# App_Board_V1_31.net
KiCad netlist of a schematic drawn in EAGLE
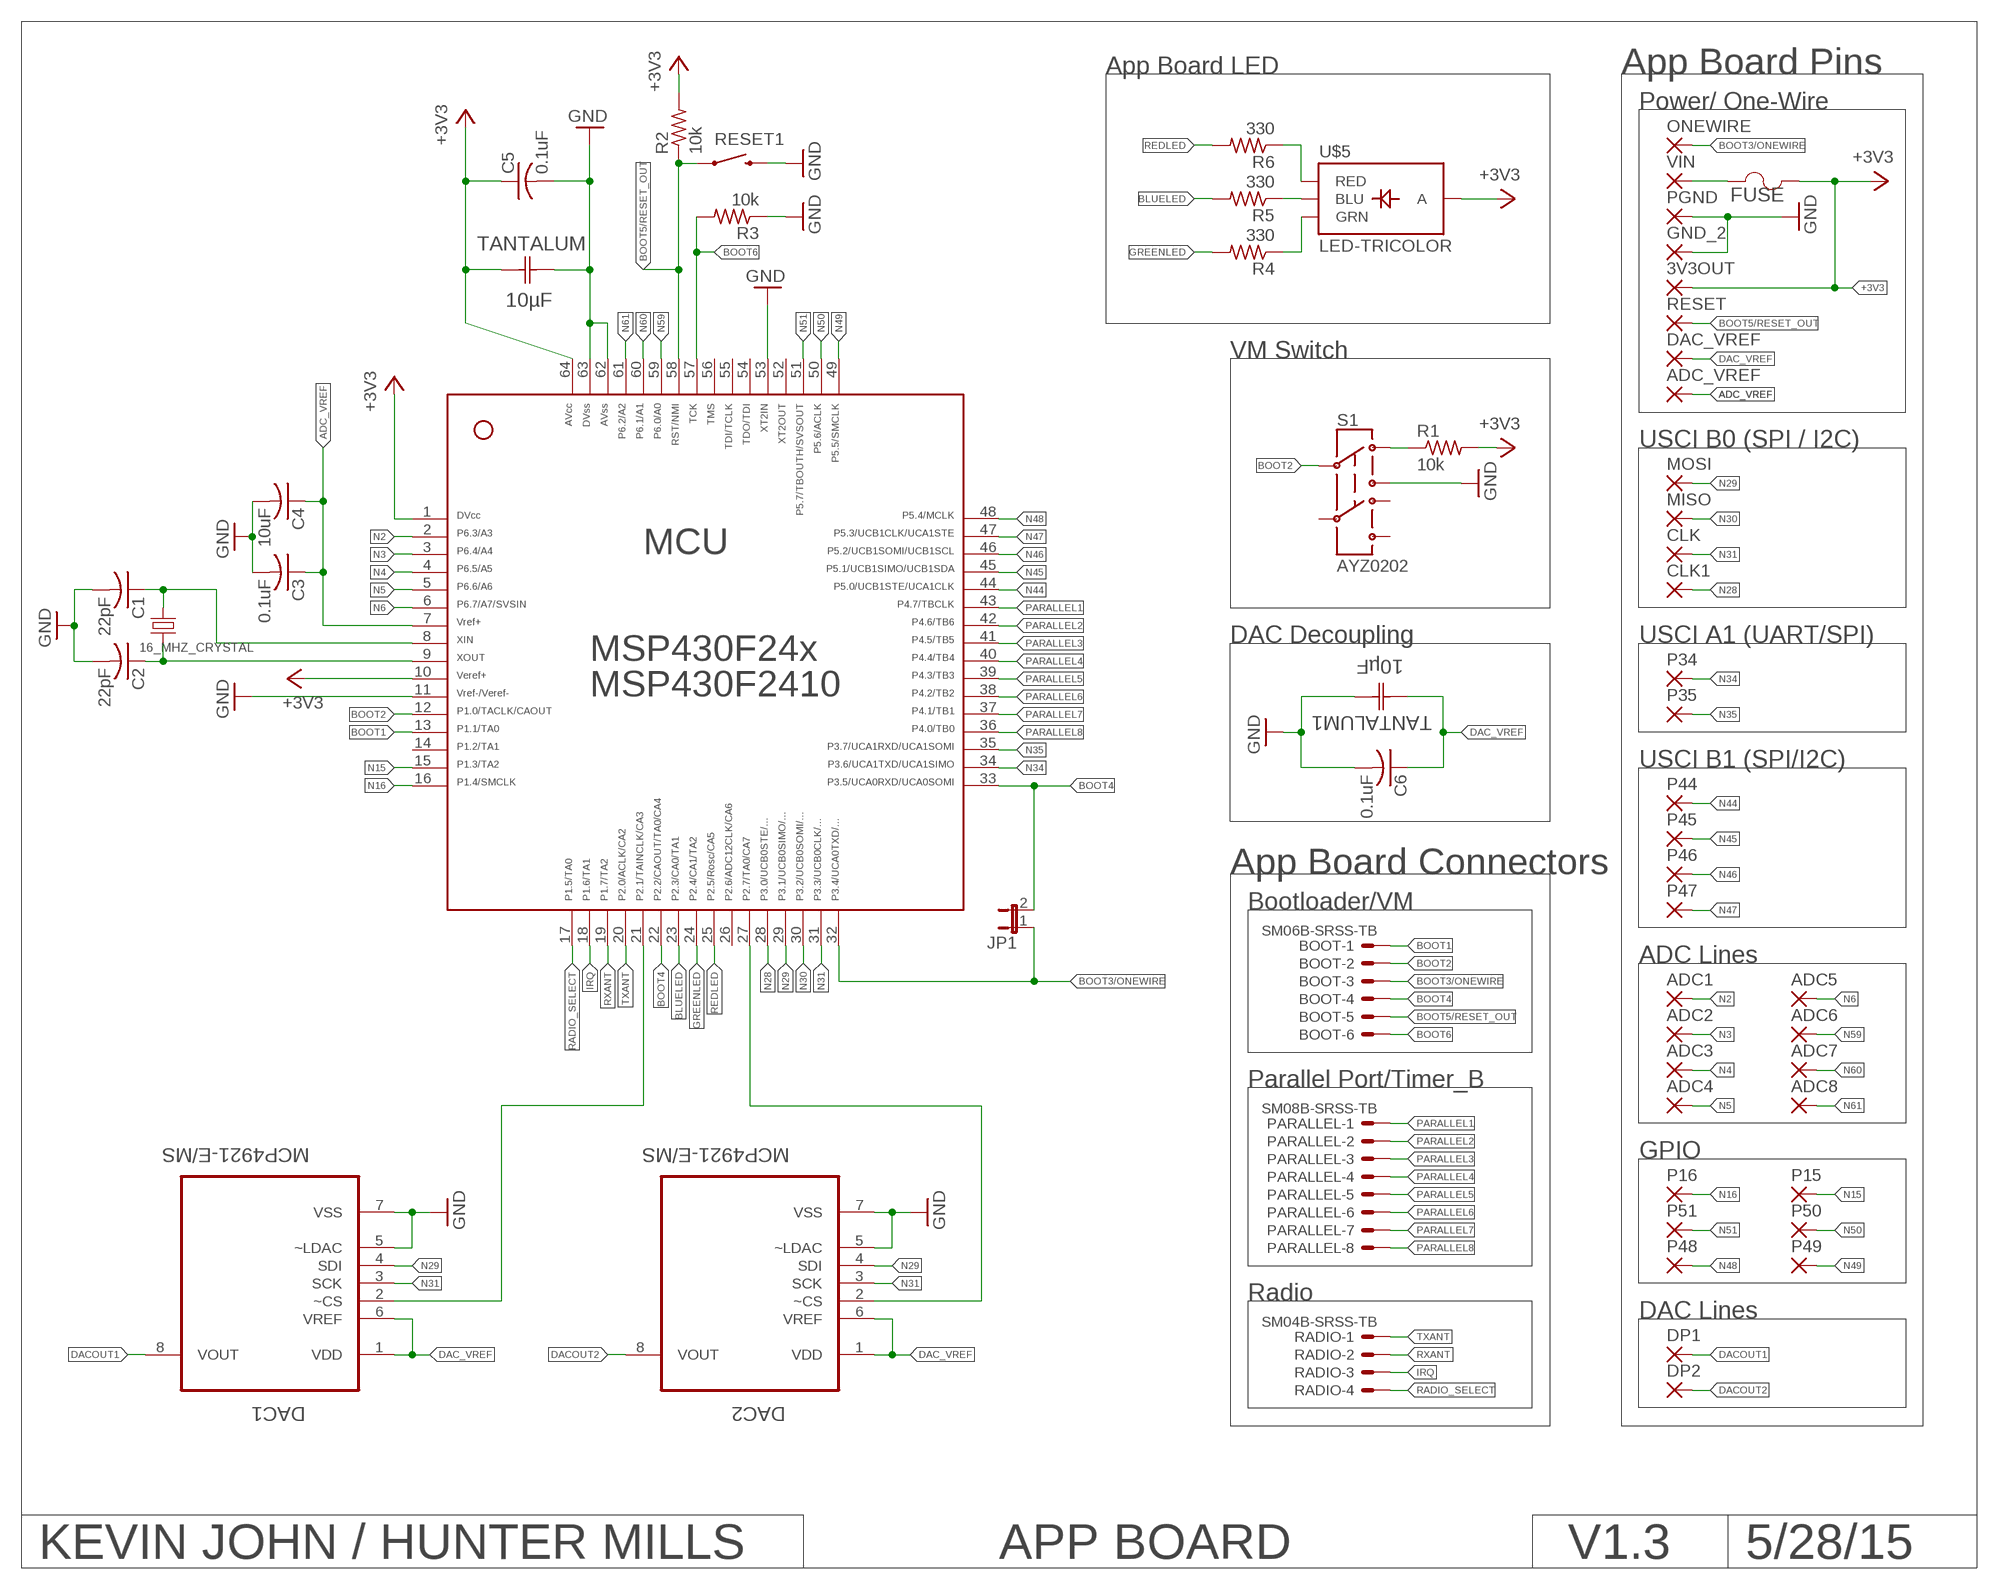
[diagram p0: schematic, sheet 1]

(export (version "E")
  (design (tool "Eeschema 10.0.6"))
  (components
    (comp (ref "3V3OUT")
      (value "1,6/0,9")
      (footprint "eagle-import:1,6_0,9")
      (libsource (lib "eagle-import") (part "1,6/0,9"))
    )
    (comp (ref "16_MHZ_CRYSTAL")
      (value "HUNTERCRYSTAL")
      (footprint "eagle-import:CRYSTAL-SMD-5X3")
      (libsource (lib "eagle-import") (part "HUNTERCRYSTAL"))
    )
    (comp (ref "ADC1")
      (value "1,6/0,9")
      (footprint "eagle-import:1,6_0,9")
      (libsource (lib "eagle-import") (part "1,6/0,9"))
    )
    (comp (ref "ADC2")
      (value "1,6/0,9")
      (footprint "eagle-import:1,6_0,9")
      (libsource (lib "eagle-import") (part "1,6/0,9"))
    )
    (comp (ref "ADC3")
      (value "1,6/0,9")
      (footprint "eagle-import:1,6_0,9")
      (libsource (lib "eagle-import") (part "1,6/0,9"))
    )
    (comp (ref "ADC4")
      (value "1,6/0,9")
      (footprint "eagle-import:1,6_0,9")
      (libsource (lib "eagle-import") (part "1,6/0,9"))
    )
    (comp (ref "ADC5")
      (value "1,6/0,9")
      (footprint "eagle-import:1,6_0,9")
      (libsource (lib "eagle-import") (part "1,6/0,9"))
    )
    (comp (ref "ADC6")
      (value "1,6/0,9")
      (footprint "eagle-import:1,6_0,9")
      (libsource (lib "eagle-import") (part "1,6/0,9"))
    )
    (comp (ref "ADC7")
      (value "1,6/0,9")
      (footprint "eagle-import:1,6_0,9")
      (libsource (lib "eagle-import") (part "1,6/0,9"))
    )
    (comp (ref "ADC8")
      (value "1,6/0,9")
      (footprint "eagle-import:1,6_0,9")
      (libsource (lib "eagle-import") (part "1,6/0,9"))
    )
    (comp (ref "ADC_VREF")
      (value "1,6/0,9")
      (footprint "eagle-import:1,6_0,9")
      (libsource (lib "eagle-import") (part "1,6/0,9"))
    )
    (comp (ref "BOOT")
      (value "SM06B-SRSS-TB")
      (footprint "eagle-import:SM06B-SRSS-TB")
      (libsource (lib "eagle-import") (part "?M06B-SRSS-TBS"))
    )
    (comp (ref "C1")
      (value "22pF")
      (footprint "eagle-import:C0805")
      (libsource (lib "eagle-import") (part "C-USC0805"))
    )
    (comp (ref "C2")
      (value "22pF")
      (footprint "eagle-import:C0805")
      (libsource (lib "eagle-import") (part "C-USC0805"))
    )
    (comp (ref "C3")
      (value "0.1uF")
      (footprint "eagle-import:C0805")
      (libsource (lib "eagle-import") (part "C-USC0805"))
    )
    (comp (ref "C4")
      (value "10uF")
      (footprint "eagle-import:C0805")
      (libsource (lib "eagle-import") (part "C-USC0805"))
    )
    (comp (ref "C5")
      (value "0.1uF")
      (footprint "eagle-import:C0805")
      (libsource (lib "eagle-import") (part "C-USC0805"))
    )
    (comp (ref "C6")
      (value "0.1uF")
      (footprint "eagle-import:C0805")
      (libsource (lib "eagle-import") (part "C-USC0805"))
    )
    (comp (ref "CLK")
      (value "1,6/0,9")
      (footprint "eagle-import:1,6_0,9")
      (libsource (lib "eagle-import") (part "1,6/0,9"))
    )
    (comp (ref "CLK1")
      (value "1,6/0,9")
      (footprint "eagle-import:1,6_0,9")
      (libsource (lib "eagle-import") (part "1,6/0,9"))
    )
    (comp (ref "DAC1")
      (value "MCP4921-E/MS")
      (footprint "eagle-import:SOP65P490X110-8N")
      (libsource (lib "eagle-import") (part "MCP4921-E/MS"))
    )
    (comp (ref "DAC2")
      (value "MCP4921-E/MS")
      (footprint "eagle-import:SOP65P490X110-8N")
      (libsource (lib "eagle-import") (part "MCP4921-E/MS"))
    )
    (comp (ref "DAC_VREF")
      (value "1,6/0,9")
      (footprint "eagle-import:1,6_0,9")
      (libsource (lib "eagle-import") (part "1,6/0,9"))
    )
    (comp (ref "DP1")
      (value "1,6/0,9")
      (footprint "eagle-import:1,6_0,9")
      (libsource (lib "eagle-import") (part "1,6/0,9"))
    )
    (comp (ref "DP2")
      (value "1,6/0,9")
      (footprint "eagle-import:1,6_0,9")
      (libsource (lib "eagle-import") (part "1,6/0,9"))
    )
    (comp (ref "FUSE")
      (value "HUNTERFUSE")
      (footprint "eagle-import:CAPC4532X254N")
      (libsource (lib "eagle-import") (part "HUNTERFUSE"))
    )
    (comp (ref "GND_2")
      (value "1,6/0,9")
      (footprint "eagle-import:1,6_0,9")
      (libsource (lib "eagle-import") (part "1,6/0,9"))
    )
    (comp (ref "JP1")
      (value "JP1E")
      (footprint "eagle-import:JP1")
      (libsource (lib "eagle-import") (part "JP1E"))
    )
    (comp (ref "MCU")
      (value "F24[X/10]---PM64")
      (footprint "eagle-import:PM_PAG64")
      (libsource (lib "eagle-import") (part "F24[X/10]---PM64"))
    )
    (comp (ref "MISO")
      (value "1,6/0,9")
      (footprint "eagle-import:1,6_0,9")
      (libsource (lib "eagle-import") (part "1,6/0,9"))
    )
    (comp (ref "MOSI")
      (value "1,6/0,9")
      (footprint "eagle-import:1,6_0,9")
      (libsource (lib "eagle-import") (part "1,6/0,9"))
    )
    (comp (ref "ONEWIRE")
      (value "1,6/0,9")
      (footprint "eagle-import:1,6_0,9")
      (libsource (lib "eagle-import") (part "1,6/0,9"))
    )
    (comp (ref "P15")
      (value "1,6/0,9")
      (footprint "eagle-import:1,6_0,9")
      (libsource (lib "eagle-import") (part "1,6/0,9"))
    )
    (comp (ref "P16")
      (value "1,6/0,9")
      (footprint "eagle-import:1,6_0,9")
      (libsource (lib "eagle-import") (part "1,6/0,9"))
    )
    (comp (ref "P34")
      (value "1,6/0,9")
      (footprint "eagle-import:1,6_0,9")
      (libsource (lib "eagle-import") (part "1,6/0,9"))
    )
    (comp (ref "P35")
      (value "1,6/0,9")
      (footprint "eagle-import:1,6_0,9")
      (libsource (lib "eagle-import") (part "1,6/0,9"))
    )
    (comp (ref "P44")
      (value "1,6/0,9")
      (footprint "eagle-import:1,6_0,9")
      (libsource (lib "eagle-import") (part "1,6/0,9"))
    )
    (comp (ref "P45")
      (value "1,6/0,9")
      (footprint "eagle-import:1,6_0,9")
      (libsource (lib "eagle-import") (part "1,6/0,9"))
    )
    (comp (ref "P46")
      (value "1,6/0,9")
      (footprint "eagle-import:1,6_0,9")
      (libsource (lib "eagle-import") (part "1,6/0,9"))
    )
    (comp (ref "P47")
      (value "1,6/0,9")
      (footprint "eagle-import:1,6_0,9")
      (libsource (lib "eagle-import") (part "1,6/0,9"))
    )
    (comp (ref "P48")
      (value "1,6/0,9")
      (footprint "eagle-import:1,6_0,9")
      (libsource (lib "eagle-import") (part "1,6/0,9"))
    )
    (comp (ref "P49")
      (value "1,6/0,9")
      (footprint "eagle-import:1,6_0,9")
      (libsource (lib "eagle-import") (part "1,6/0,9"))
    )
    (comp (ref "P50")
      (value "1,6/0,9")
      (footprint "eagle-import:1,6_0,9")
      (libsource (lib "eagle-import") (part "1,6/0,9"))
    )
    (comp (ref "P51")
      (value "1,6/0,9")
      (footprint "eagle-import:1,6_0,9")
      (libsource (lib "eagle-import") (part "1,6/0,9"))
    )
    (comp (ref "PARALLEL")
      (value "SM08B-SRSS-TB")
      (footprint "eagle-import:SM08B-SRSS-TB")
      (libsource (lib "eagle-import") (part "?M08B-SRSS-TBS"))
    )
    (comp (ref "PGND")
      (value "1,6/0,9")
      (footprint "eagle-import:1,6_0,9")
      (libsource (lib "eagle-import") (part "1,6/0,9"))
    )
    (comp (ref "R1")
      (value "10k")
      (footprint "eagle-import:R0603")
      (libsource (lib "eagle-import") (part "R-US_R0603"))
    )
    (comp (ref "R2")
      (value "10k")
      (footprint "eagle-import:R0603")
      (libsource (lib "eagle-import") (part "R-US_R0603"))
    )
    (comp (ref "R3")
      (value "10k")
      (footprint "eagle-import:R0603")
      (libsource (lib "eagle-import") (part "R-US_R0603"))
    )
    (comp (ref "R4")
      (value "330")
      (footprint "eagle-import:R0603")
      (libsource (lib "eagle-import") (part "R-US_R0603"))
    )
    (comp (ref "R5")
      (value "330")
      (footprint "eagle-import:R0603")
      (libsource (lib "eagle-import") (part "R-US_R0603"))
    )
    (comp (ref "R6")
      (value "330")
      (footprint "eagle-import:R0603")
      (libsource (lib "eagle-import") (part "R-US_R0603"))
    )
    (comp (ref "RADIO")
      (value "SM04B-SRSS-TB")
      (footprint "eagle-import:SM04B-SRSS-TB")
      (libsource (lib "eagle-import") (part "?M04B-SRSS-TBS"))
    )
    (comp (ref "RESET")
      (value "1,6/0,9")
      (footprint "eagle-import:1,6_0,9")
      (libsource (lib "eagle-import") (part "1,6/0,9"))
    )
    (comp (ref "RESET1")
      (value "SWITCH-MOMENTARY-2SMD")
      (footprint "eagle-import:TACTILE-SWITCH-SMD")
      (libsource (lib "eagle-import") (part "SWITCH-MOMENTARY-2SMD"))
    )
    (comp (ref "S1")
      (value "AYZ0202")
      (footprint "eagle-import:AYZ0202")
      (libsource (lib "eagle-import") (part "AYZ0202"))
    )
    (comp (ref "TANTALUM")
      (value "10µF")
      (footprint "eagle-import:CAPCP3528X120N")
      (fields (field (name "MPN") "TAJT106K016R"))
      (libsource (lib "eagle-import") (part "TAJT106K016R"))
    )
    (comp (ref "TANTALUM1")
      (value "10µF")
      (footprint "eagle-import:CAPCP3528X120N")
      (fields (field (name "MPN") "TAJT106K016R"))
      (libsource (lib "eagle-import") (part "TAJT106K016R"))
    )
    (comp (ref "U$5")
      (value "LED-TRICOLOR")
      (footprint "eagle-import:LED-TRICOLOR-SMD")
      (libsource (lib "eagle-import") (part "LED-TRICOLOR"))
    )
    (comp (ref "VIN")
      (value "1,6/0,9")
      (footprint "eagle-import:1,6_0,9")
      (libsource (lib "eagle-import") (part "1,6/0,9"))
    )
  )
  (nets
    (net (code "1") (name "+3V3") (class "Default")
      (node (ref "3V3OUT") (pin "1") (pinfunction "P_1") (pintype "passive"))
      (node (ref "C5") (pin "1") (pinfunction "1_1") (pintype "passive"))
      (node (ref "FUSE") (pin "2") (pinfunction "2_2") (pintype "passive"))
      (node (ref "MCU") (pin "1") (pinfunction "1_1") (pintype "power_in"))
      (node (ref "MCU") (pin "10") (pinfunction "10_10") (pintype "output"))
      (node (ref "MCU") (pin "64") (pinfunction "64_64") (pintype "power_in"))
      (node (ref "R1") (pin "2") (pinfunction "2_2") (pintype "passive"))
      (node (ref "R2") (pin "2") (pinfunction "2_2") (pintype "passive"))
      (node (ref "TANTALUM") (pin "1") (pinfunction "C1_1") (pintype "passive"))
      (node (ref "U$5") (pin "A") (pinfunction "A_A") (pintype "bidirectional"))
    )
    (net (code "2") (name "ADC_VREF") (class "Default")
      (node (ref "ADC_VREF") (pin "1") (pinfunction "P_1") (pintype "passive"))
      (node (ref "C3") (pin "1") (pinfunction "1_1") (pintype "passive"))
      (node (ref "C4") (pin "1") (pinfunction "1_1") (pintype "passive"))
      (node (ref "MCU") (pin "7") (pinfunction "7_7") (pintype "output"))
    )
    (net (code "3") (name "BLUELED") (class "Default")
      (node (ref "MCU") (pin "23") (pinfunction "23_23") (pintype "bidirectional"))
      (node (ref "R5") (pin "2") (pinfunction "2_2") (pintype "passive"))
    )
    (net (code "4") (name "BOOT1") (class "Default")
      (node (ref "BOOT") (pin "1") (pinfunction "S_1") (pintype "passive"))
      (node (ref "MCU") (pin "13") (pinfunction "13_13") (pintype "bidirectional"))
    )
    (net (code "5") (name "BOOT2") (class "Default")
      (node (ref "BOOT") (pin "2") (pinfunction "S_2") (pintype "passive"))
      (node (ref "MCU") (pin "12") (pinfunction "12_12") (pintype "bidirectional"))
      (node (ref "S1") (pin "2") (pinfunction "2_2") (pintype "bidirectional"))
    )
    (net (code "6") (name "BOOT3{slash}ONEWIRE") (class "Default")
      (node (ref "BOOT") (pin "3") (pinfunction "S_3") (pintype "passive"))
      (node (ref "JP1") (pin "1") (pinfunction "1_1") (pintype "passive"))
      (node (ref "MCU") (pin "32") (pinfunction "32_32") (pintype "bidirectional"))
      (node (ref "ONEWIRE") (pin "1") (pinfunction "P_1") (pintype "passive"))
    )
    (net (code "7") (name "BOOT4") (class "Default")
      (node (ref "BOOT") (pin "4") (pinfunction "S_4") (pintype "passive"))
      (node (ref "JP1") (pin "2") (pinfunction "2_2") (pintype "passive"))
      (node (ref "MCU") (pin "22") (pinfunction "22_22") (pintype "bidirectional"))
      (node (ref "MCU") (pin "33") (pinfunction "33_33") (pintype "bidirectional"))
    )
    (net (code "8") (name "BOOT5{slash}RESET_OUT") (class "Default")
      (node (ref "BOOT") (pin "5") (pinfunction "S_5") (pintype "passive"))
      (node (ref "MCU") (pin "58") (pinfunction "58_58") (pintype "input"))
      (node (ref "R2") (pin "1") (pinfunction "1_1") (pintype "passive"))
      (node (ref "RESET") (pin "1") (pinfunction "P_1") (pintype "passive"))
      (node (ref "RESET1") (pin "1") (pinfunction "1_1") (pintype "passive"))
    )
    (net (code "9") (name "BOOT6") (class "Default")
      (node (ref "BOOT") (pin "6") (pinfunction "S_6") (pintype "passive"))
      (node (ref "MCU") (pin "57") (pinfunction "57_57") (pintype "input"))
      (node (ref "R3") (pin "2") (pinfunction "2_2") (pintype "passive"))
    )
    (net (code "10") (name "DACOUT1") (class "Default")
      (node (ref "DAC1") (pin "8") (pinfunction "VOUT_8") (pintype "output"))
      (node (ref "DP1") (pin "1") (pinfunction "P_1") (pintype "passive"))
    )
    (net (code "11") (name "DACOUT2") (class "Default")
      (node (ref "DAC2") (pin "8") (pinfunction "VOUT_8") (pintype "output"))
      (node (ref "DP2") (pin "1") (pinfunction "P_1") (pintype "passive"))
    )
    (net (code "12") (name "DAC_VREF") (class "Default")
      (node (ref "C6") (pin "1") (pinfunction "1_1") (pintype "passive"))
      (node (ref "DAC1") (pin "1") (pinfunction "VDD_1") (pintype "power_in"))
      (node (ref "DAC1") (pin "6") (pinfunction "VREF_6") (pintype "input"))
      (node (ref "DAC2") (pin "1") (pinfunction "VDD_1") (pintype "power_in"))
      (node (ref "DAC2") (pin "6") (pinfunction "VREF_6") (pintype "input"))
      (node (ref "DAC_VREF") (pin "1") (pinfunction "P_1") (pintype "passive"))
      (node (ref "TANTALUM1") (pin "1") (pinfunction "C1_1") (pintype "passive"))
    )
    (net (code "13") (name "GND") (class "Default")
      (node (ref "C1") (pin "2") (pinfunction "2_2") (pintype "passive"))
      (node (ref "C2") (pin "2") (pinfunction "2_2") (pintype "passive"))
      (node (ref "C3") (pin "2") (pinfunction "2_2") (pintype "passive"))
      (node (ref "C4") (pin "2") (pinfunction "2_2") (pintype "passive"))
      (node (ref "C5") (pin "2") (pinfunction "2_2") (pintype "passive"))
      (node (ref "C6") (pin "2") (pinfunction "2_2") (pintype "passive"))
      (node (ref "DAC1") (pin "5") (pinfunction "~{LDAC}_5") (pintype "input"))
      (node (ref "DAC1") (pin "7") (pinfunction "VSS_7") (pintype "power_in"))
      (node (ref "DAC2") (pin "5") (pinfunction "~{LDAC}_5") (pintype "input"))
      (node (ref "DAC2") (pin "7") (pinfunction "VSS_7") (pintype "power_in"))
      (node (ref "GND_2") (pin "1") (pinfunction "P_1") (pintype "passive"))
      (node (ref "MCU") (pin "11") (pinfunction "11_11") (pintype "input"))
      (node (ref "MCU") (pin "53") (pinfunction "53_53") (pintype "input"))
      (node (ref "MCU") (pin "62") (pinfunction "62_62") (pintype "power_in"))
      (node (ref "MCU") (pin "63") (pinfunction "63_63") (pintype "power_in"))
      (node (ref "PGND") (pin "1") (pinfunction "P_1") (pintype "passive"))
      (node (ref "R3") (pin "1") (pinfunction "1_1") (pintype "passive"))
      (node (ref "RESET1") (pin "3") (pinfunction "2_3") (pintype "passive"))
      (node (ref "S1") (pin "1") (pinfunction "3_1") (pintype "bidirectional"))
      (node (ref "TANTALUM") (pin "2") (pinfunction "C2_2") (pintype "passive"))
      (node (ref "TANTALUM1") (pin "2") (pinfunction "C2_2") (pintype "passive"))
    )
    (net (code "14") (name "GREENLED") (class "Default")
      (node (ref "MCU") (pin "24") (pinfunction "24_24") (pintype "bidirectional"))
      (node (ref "R4") (pin "2") (pinfunction "2_2") (pintype "passive"))
    )
    (net (code "15") (name "IRQ") (class "Default")
      (node (ref "MCU") (pin "18") (pinfunction "18_18") (pintype "bidirectional"))
      (node (ref "RADIO") (pin "3") (pinfunction "S_3") (pintype "passive"))
    )
    (net (code "16") (name "N2") (class "Default")
      (node (ref "ADC1") (pin "1") (pinfunction "P_1") (pintype "passive"))
      (node (ref "MCU") (pin "2") (pinfunction "2_2") (pintype "bidirectional"))
    )
    (net (code "17") (name "N3") (class "Default")
      (node (ref "ADC2") (pin "1") (pinfunction "P_1") (pintype "passive"))
      (node (ref "MCU") (pin "3") (pinfunction "3_3") (pintype "bidirectional"))
    )
    (net (code "18") (name "N4") (class "Default")
      (node (ref "ADC3") (pin "1") (pinfunction "P_1") (pintype "passive"))
      (node (ref "MCU") (pin "4") (pinfunction "4_4") (pintype "bidirectional"))
    )
    (net (code "19") (name "N5") (class "Default")
      (node (ref "ADC4") (pin "1") (pinfunction "P_1") (pintype "passive"))
      (node (ref "MCU") (pin "5") (pinfunction "5_5") (pintype "bidirectional"))
    )
    (net (code "20") (name "N6") (class "Default")
      (node (ref "ADC5") (pin "1") (pinfunction "P_1") (pintype "passive"))
      (node (ref "MCU") (pin "6") (pinfunction "6_6") (pintype "bidirectional"))
    )
    (net (code "21") (name "N15") (class "Default")
      (node (ref "MCU") (pin "15") (pinfunction "15_15") (pintype "bidirectional"))
      (node (ref "P15") (pin "1") (pinfunction "P_1") (pintype "passive"))
    )
    (net (code "22") (name "N16") (class "Default")
      (node (ref "MCU") (pin "16") (pinfunction "16_16") (pintype "bidirectional"))
      (node (ref "P16") (pin "1") (pinfunction "P_1") (pintype "passive"))
    )
    (net (code "23") (name "N28") (class "Default")
      (node (ref "CLK1") (pin "1") (pinfunction "P_1") (pintype "passive"))
      (node (ref "MCU") (pin "28") (pinfunction "28_28") (pintype "bidirectional"))
    )
    (net (code "24") (name "N29") (class "Default")
      (node (ref "DAC1") (pin "4") (pinfunction "SDI_4") (pintype "input"))
      (node (ref "DAC2") (pin "4") (pinfunction "SDI_4") (pintype "input"))
      (node (ref "MCU") (pin "29") (pinfunction "29_29") (pintype "bidirectional"))
      (node (ref "MOSI") (pin "1") (pinfunction "P_1") (pintype "passive"))
    )
    (net (code "25") (name "N30") (class "Default")
      (node (ref "MCU") (pin "30") (pinfunction "30_30") (pintype "bidirectional"))
      (node (ref "MISO") (pin "1") (pinfunction "P_1") (pintype "passive"))
    )
    (net (code "26") (name "N31") (class "Default")
      (node (ref "CLK") (pin "1") (pinfunction "P_1") (pintype "passive"))
      (node (ref "DAC1") (pin "3") (pinfunction "SCK_3") (pintype "input"))
      (node (ref "DAC2") (pin "3") (pinfunction "SCK_3") (pintype "input"))
      (node (ref "MCU") (pin "31") (pinfunction "31_31") (pintype "bidirectional"))
    )
    (net (code "27") (name "N34") (class "Default")
      (node (ref "MCU") (pin "34") (pinfunction "34_34") (pintype "bidirectional"))
      (node (ref "P34") (pin "1") (pinfunction "P_1") (pintype "passive"))
    )
    (net (code "28") (name "N35") (class "Default")
      (node (ref "MCU") (pin "35") (pinfunction "35_35") (pintype "bidirectional"))
      (node (ref "P35") (pin "1") (pinfunction "P_1") (pintype "passive"))
    )
    (net (code "29") (name "N44") (class "Default")
      (node (ref "MCU") (pin "44") (pinfunction "44_44") (pintype "bidirectional"))
      (node (ref "P44") (pin "1") (pinfunction "P_1") (pintype "passive"))
    )
    (net (code "30") (name "N45") (class "Default")
      (node (ref "MCU") (pin "45") (pinfunction "45_45") (pintype "bidirectional"))
      (node (ref "P45") (pin "1") (pinfunction "P_1") (pintype "passive"))
    )
    (net (code "31") (name "N46") (class "Default")
      (node (ref "MCU") (pin "46") (pinfunction "46_46") (pintype "bidirectional"))
      (node (ref "P46") (pin "1") (pinfunction "P_1") (pintype "passive"))
    )
    (net (code "32") (name "N47") (class "Default")
      (node (ref "MCU") (pin "47") (pinfunction "47_47") (pintype "bidirectional"))
      (node (ref "P47") (pin "1") (pinfunction "P_1") (pintype "passive"))
    )
    (net (code "33") (name "N48") (class "Default")
      (node (ref "MCU") (pin "48") (pinfunction "48_48") (pintype "bidirectional"))
      (node (ref "P48") (pin "1") (pinfunction "P_1") (pintype "passive"))
    )
    (net (code "34") (name "N49") (class "Default")
      (node (ref "MCU") (pin "49") (pinfunction "49_49") (pintype "bidirectional"))
      (node (ref "P49") (pin "1") (pinfunction "P_1") (pintype "passive"))
    )
    (net (code "35") (name "N50") (class "Default")
      (node (ref "MCU") (pin "50") (pinfunction "50_50") (pintype "bidirectional"))
      (node (ref "P50") (pin "1") (pinfunction "P_1") (pintype "passive"))
    )
    (net (code "36") (name "N51") (class "Default")
      (node (ref "MCU") (pin "51") (pinfunction "51_51") (pintype "bidirectional"))
      (node (ref "P51") (pin "1") (pinfunction "P_1") (pintype "passive"))
    )
    (net (code "37") (name "N59") (class "Default")
      (node (ref "ADC6") (pin "1") (pinfunction "P_1") (pintype "passive"))
      (node (ref "MCU") (pin "59") (pinfunction "59_59") (pintype "bidirectional"))
    )
    (net (code "38") (name "N60") (class "Default")
      (node (ref "ADC7") (pin "1") (pinfunction "P_1") (pintype "passive"))
      (node (ref "MCU") (pin "60") (pinfunction "60_60") (pintype "bidirectional"))
    )
    (net (code "39") (name "N61") (class "Default")
      (node (ref "ADC8") (pin "1") (pinfunction "P_1") (pintype "passive"))
      (node (ref "MCU") (pin "61") (pinfunction "61_61") (pintype "bidirectional"))
    )
    (net (code "40") (name "Net-(16_MHZ_CRYSTAL-Pad1)") (class "Default")
      (node (ref "16_MHZ_CRYSTAL") (pin "1") (pinfunction "1_1") (pintype "passive"))
      (node (ref "C2") (pin "1") (pinfunction "1_1") (pintype "passive"))
      (node (ref "MCU") (pin "9") (pinfunction "9_9") (pintype "output"))
    )
    (net (code "41") (name "Net-(16_MHZ_CRYSTAL-Pad3)") (class "Default")
      (node (ref "16_MHZ_CRYSTAL") (pin "3") (pinfunction "3_3") (pintype "passive"))
      (node (ref "C1") (pin "1") (pinfunction "1_1") (pintype "passive"))
      (node (ref "MCU") (pin "8") (pinfunction "8_8") (pintype "input"))
    )
    (net (code "42") (name "Net-(DAC1-~{CS})") (class "Default")
      (node (ref "DAC1") (pin "2") (pinfunction "~{CS}_2") (pintype "input"))
      (node (ref "MCU") (pin "21") (pinfunction "21_21") (pintype "bidirectional"))
    )
    (net (code "43") (name "Net-(DAC2-~{CS})") (class "Default")
      (node (ref "DAC2") (pin "2") (pinfunction "~{CS}_2") (pintype "input"))
      (node (ref "MCU") (pin "27") (pinfunction "27_27") (pintype "bidirectional"))
    )
    (net (code "44") (name "Net-(S1-1)") (class "Default")
      (node (ref "R1") (pin "1") (pinfunction "1_1") (pintype "passive"))
      (node (ref "S1") (pin "3") (pinfunction "1_3") (pintype "bidirectional"))
    )
    (net (code "45") (name "Net-(U$5-BLU)") (class "Default")
      (node (ref "R5") (pin "1") (pinfunction "1_1") (pintype "passive"))
      (node (ref "U$5") (pin "B") (pinfunction "BLU_B") (pintype "bidirectional"))
    )
    (net (code "46") (name "Net-(U$5-GRN)") (class "Default")
      (node (ref "R4") (pin "1") (pinfunction "1_1") (pintype "passive"))
      (node (ref "U$5") (pin "G") (pinfunction "GRN_G") (pintype "bidirectional"))
    )
    (net (code "47") (name "Net-(U$5-RED)") (class "Default")
      (node (ref "R6") (pin "1") (pinfunction "1_1") (pintype "passive"))
      (node (ref "U$5") (pin "R") (pinfunction "RED_R") (pintype "bidirectional"))
    )
    (net (code "48") (name "Net-(VIN-P)") (class "Default")
      (node (ref "FUSE") (pin "1") (pinfunction "1_1") (pintype "passive"))
      (node (ref "VIN") (pin "1") (pinfunction "P_1") (pintype "passive"))
    )
    (net (code "49") (name "PARALLEL1") (class "Default")
      (node (ref "MCU") (pin "43") (pinfunction "43_43") (pintype "bidirectional"))
      (node (ref "PARALLEL") (pin "1") (pinfunction "S_1") (pintype "passive"))
    )
    (net (code "50") (name "PARALLEL2") (class "Default")
      (node (ref "MCU") (pin "42") (pinfunction "42_42") (pintype "bidirectional"))
      (node (ref "PARALLEL") (pin "2") (pinfunction "S_2") (pintype "passive"))
    )
    (net (code "51") (name "PARALLEL3") (class "Default")
      (node (ref "MCU") (pin "41") (pinfunction "41_41") (pintype "bidirectional"))
      (node (ref "PARALLEL") (pin "3") (pinfunction "S_3") (pintype "passive"))
    )
    (net (code "52") (name "PARALLEL4") (class "Default")
      (node (ref "MCU") (pin "40") (pinfunction "40_40") (pintype "bidirectional"))
      (node (ref "PARALLEL") (pin "4") (pinfunction "S_4") (pintype "passive"))
    )
    (net (code "53") (name "PARALLEL5") (class "Default")
      (node (ref "MCU") (pin "39") (pinfunction "39_39") (pintype "bidirectional"))
      (node (ref "PARALLEL") (pin "5") (pinfunction "S_5") (pintype "passive"))
    )
    (net (code "54") (name "PARALLEL6") (class "Default")
      (node (ref "MCU") (pin "38") (pinfunction "38_38") (pintype "bidirectional"))
      (node (ref "PARALLEL") (pin "6") (pinfunction "S_6") (pintype "passive"))
    )
    (net (code "55") (name "PARALLEL7") (class "Default")
      (node (ref "MCU") (pin "37") (pinfunction "37_37") (pintype "bidirectional"))
      (node (ref "PARALLEL") (pin "7") (pinfunction "S_7") (pintype "passive"))
    )
    (net (code "56") (name "PARALLEL8") (class "Default")
      (node (ref "MCU") (pin "36") (pinfunction "36_36") (pintype "bidirectional"))
      (node (ref "PARALLEL") (pin "8") (pinfunction "S_8") (pintype "passive"))
    )
    (net (code "57") (name "RADIO_SELECT") (class "Default")
      (node (ref "MCU") (pin "17") (pinfunction "17_17") (pintype "bidirectional"))
      (node (ref "RADIO") (pin "4") (pinfunction "S_4") (pintype "passive"))
    )
    (net (code "58") (name "REDLED") (class "Default")
      (node (ref "MCU") (pin "25") (pinfunction "25_25") (pintype "bidirectional"))
      (node (ref "R6") (pin "2") (pinfunction "2_2") (pintype "passive"))
    )
    (net (code "59") (name "RXANT") (class "Default")
      (node (ref "MCU") (pin "19") (pinfunction "19_19") (pintype "bidirectional"))
      (node (ref "RADIO") (pin "2") (pinfunction "S_2") (pintype "passive"))
    )
    (net (code "60") (name "TXANT") (class "Default")
      (node (ref "MCU") (pin "20") (pinfunction "20_20") (pintype "bidirectional"))
      (node (ref "RADIO") (pin "1") (pinfunction "S_1") (pintype "passive"))
    )
    (net (code "61") (name "unconnected-(MCU-Pad14)") (class "Default")
      (node (ref "MCU") (pin "14") (pinfunction "14_14") (pintype "bidirectional"))
    )
    (net (code "62") (name "unconnected-(MCU-Pad26)") (class "Default")
      (node (ref "MCU") (pin "26") (pinfunction "26_26") (pintype "bidirectional"))
    )
    (net (code "63") (name "unconnected-(MCU-Pad52)") (class "Default")
      (node (ref "MCU") (pin "52") (pinfunction "52_52") (pintype "output"))
    )
    (net (code "64") (name "unconnected-(MCU-Pad54)") (class "Default")
      (node (ref "MCU") (pin "54") (pinfunction "54_54") (pintype "bidirectional"))
    )
    (net (code "65") (name "unconnected-(MCU-Pad55)") (class "Default")
      (node (ref "MCU") (pin "55") (pinfunction "55_55") (pintype "input"))
    )
    (net (code "66") (name "unconnected-(MCU-Pad56)") (class "Default")
      (node (ref "MCU") (pin "56") (pinfunction "56_56") (pintype "input"))
    )
    (net (code "67") (name "unconnected-(S1-4-Pad6)") (class "Default")
      (node (ref "S1") (pin "6") (pinfunction "4_6") (pintype "bidirectional"))
    )
    (net (code "68") (name "unconnected-(S1-6-Pad4)") (class "Default")
      (node (ref "S1") (pin "4") (pinfunction "6_4") (pintype "bidirectional"))
    )
    (net (code "69") (name "unconnected-(S1-Pad5)") (class "Default")
      (node (ref "S1") (pin "5") (pinfunction "5_5") (pintype "bidirectional"))
    )
  )
)
